# powermeter.net
KiCad netlist of a schematic drawn in EAGLE
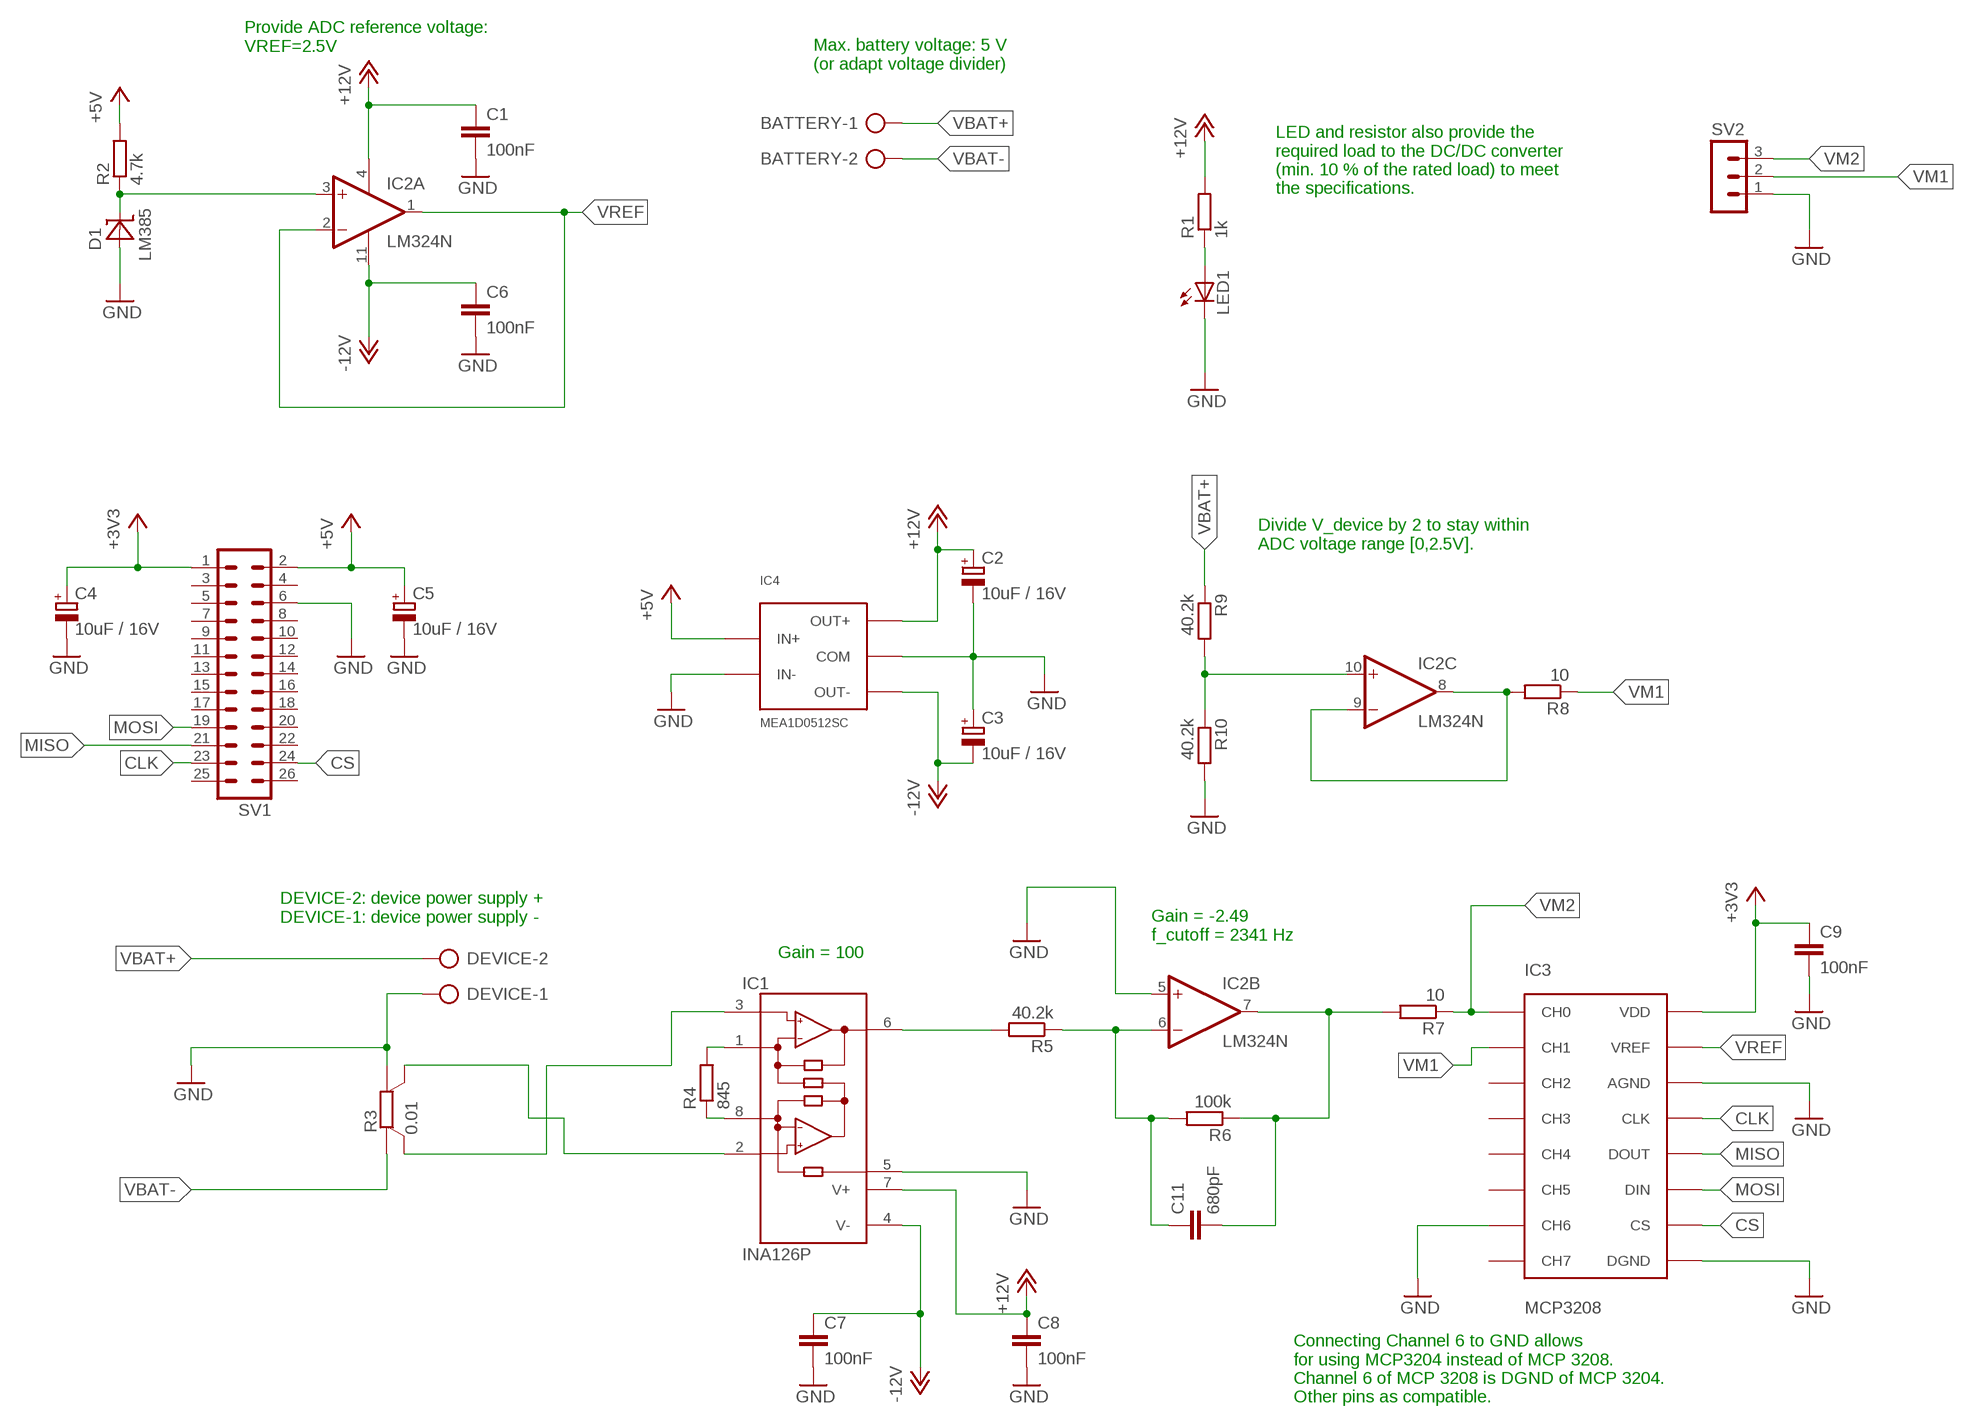
[diagram p0: schematic, sheet 1]

(export (version "E")
  (design (tool "Eeschema 10.0.6"))
  (components
    (comp (ref "BATTERY")
      (value "AK500/2")
      (footprint "eagle-import:AK500_2")
      (libsource (lib "eagle-import") (part "AK500/2"))
    )
    (comp (ref "C1")
      (value "100nF")
      (footprint "eagle-import:C050-024X044")
      (libsource (lib "eagle-import") (part "C-EU050-024X044"))
    )
    (comp (ref "C2")
      (value "10uF / 16V")
      (footprint "eagle-import:E2,5-6")
      (libsource (lib "eagle-import") (part "CPOL-EUE2.5-6"))
    )
    (comp (ref "C3")
      (value "10uF / 16V")
      (footprint "eagle-import:E2,5-6")
      (libsource (lib "eagle-import") (part "CPOL-EUE2.5-6"))
    )
    (comp (ref "C4")
      (value "10uF / 16V")
      (footprint "eagle-import:E2,5-6")
      (libsource (lib "eagle-import") (part "CPOL-EUE2.5-6"))
    )
    (comp (ref "C5")
      (value "10uF / 16V")
      (footprint "eagle-import:E2,5-6")
      (libsource (lib "eagle-import") (part "CPOL-EUE2.5-6"))
    )
    (comp (ref "C6")
      (value "100nF")
      (footprint "eagle-import:C050-024X044")
      (libsource (lib "eagle-import") (part "C-EU050-024X044"))
    )
    (comp (ref "C7")
      (value "100nF")
      (footprint "eagle-import:C050-024X044")
      (libsource (lib "eagle-import") (part "C-EU050-024X044"))
    )
    (comp (ref "C8")
      (value "100nF")
      (footprint "eagle-import:C050-024X044")
      (libsource (lib "eagle-import") (part "C-EU050-024X044"))
    )
    (comp (ref "C9")
      (value "100nF")
      (footprint "eagle-import:C050-024X044")
      (libsource (lib "eagle-import") (part "C-EU050-024X044"))
    )
    (comp (ref "C11")
      (value "680pF")
      (footprint "eagle-import:C050-050X075")
      (libsource (lib "eagle-import") (part "C-EU050-050X075"))
    )
    (comp (ref "D1")
      (value "LM385")
      (footprint "eagle-import:TO-92")
      (libsource (lib "eagle-import") (part "LM385"))
    )
    (comp (ref "DEVICE")
      (value "AK500/2")
      (footprint "eagle-import:AK500_2")
      (libsource (lib "eagle-import") (part "AK500/2"))
    )
    (comp (ref "IC1")
      (value "INA126P")
      (footprint "eagle-import:DIL08")
      (fields (field (name "MF") "TEXAS INSTRUMENT CONNECTORS"))
      (libsource (lib "eagle-import") (part "INA126P"))
    )
    (comp (ref "IC2")
      (value "LM324N")
      (footprint "eagle-import:DIL14")
      (libsource (lib "eagle-import") (part "LM324N"))
    )
    (comp (ref "IC3")
      (value "MCP3208")
      (footprint "eagle-import:DIL16")
      (libsource (lib "eagle-import") (part "MCP3208"))
    )
    (comp (ref "IC4")
      (value "MEA1D0512SC")
      (footprint "eagle-import:MEA1")
      (libsource (lib "eagle-import") (part "MEA1"))
    )
    (comp (ref "LED1")
      (value "LED3MM")
      (footprint "eagle-import:LED3MM")
      (libsource (lib "eagle-import") (part "LED3MM"))
    )
    (comp (ref "R1")
      (value "1k")
      (footprint "eagle-import:0207_7")
      (libsource (lib "eagle-import") (part "R-EU_0207/7"))
    )
    (comp (ref "R2")
      (value "4.7k")
      (footprint "eagle-import:0207_7")
      (libsource (lib "eagle-import") (part "R-EU_0207/7"))
    )
    (comp (ref "R3")
      (value "0.01")
      (footprint "eagle-import:PBV")
      (libsource (lib "eagle-import") (part "PBV"))
    )
    (comp (ref "R4")
      (value "845")
      (footprint "eagle-import:0207_7")
      (libsource (lib "eagle-import") (part "R-EU_0207/7"))
    )
    (comp (ref "R5")
      (value "40.2k")
      (footprint "eagle-import:0207_7")
      (libsource (lib "eagle-import") (part "R-EU_0207/7"))
    )
    (comp (ref "R6")
      (value "100k")
      (footprint "eagle-import:0207_7")
      (libsource (lib "eagle-import") (part "R-EU_0207/7"))
    )
    (comp (ref "R7")
      (value "10")
      (footprint "eagle-import:0207_7")
      (libsource (lib "eagle-import") (part "R-EU_0207/7"))
    )
    (comp (ref "R8")
      (value "10")
      (footprint "eagle-import:0207_7")
      (libsource (lib "eagle-import") (part "R-EU_0207/7"))
    )
    (comp (ref "R9")
      (value "40.2k")
      (footprint "eagle-import:0207_7")
      (libsource (lib "eagle-import") (part "R-EU_0207/7"))
    )
    (comp (ref "R10")
      (value "40.2k")
      (footprint "eagle-import:0207_7")
      (libsource (lib "eagle-import") (part "R-EU_0207/7"))
    )
    (comp (ref "SV1")
      (value "ML26")
      (footprint "eagle-import:ML26")
      (libsource (lib "eagle-import") (part "ML26"))
    )
    (comp (ref "SV2")
      (value "MA03-1")
      (footprint "eagle-import:MA03-1")
      (libsource (lib "eagle-import") (part "MA03-1"))
    )
  )
  (nets
    (net (code "1") (name "+3V3") (class "Default")
      (node (ref "C4") (pin "+") (pinfunction "+_+") (pintype "passive"))
      (node (ref "C9") (pin "1") (pinfunction "1_1") (pintype "passive"))
      (node (ref "IC3") (pin "VDD") (pinfunction "VDD_VDD") (pintype "power_in"))
      (node (ref "SV1") (pin "1") (pinfunction "1_1") (pintype "passive"))
    )
    (net (code "2") (name "+5V") (class "Default")
      (node (ref "C5") (pin "+") (pinfunction "+_+") (pintype "passive"))
      (node (ref "IC4") (pin "P$IN+") (pinfunction "IN+_P$IN+") (pintype "power_in"))
      (node (ref "R2") (pin "2") (pinfunction "2_2") (pintype "passive"))
      (node (ref "SV1") (pin "2") (pinfunction "2_2") (pintype "passive"))
    )
    (net (code "3") (name "+12V") (class "Default")
      (node (ref "C1") (pin "1") (pinfunction "1_1") (pintype "passive"))
      (node (ref "C2") (pin "+") (pinfunction "+_+") (pintype "passive"))
      (node (ref "C8") (pin "1") (pinfunction "1_1") (pintype "passive"))
      (node (ref "IC1") (pin "7") (pinfunction "V+_7") (pintype "power_in"))
      (node (ref "IC2") (pin "4") (pinfunction "V+_4") (pintype "power_in"))
      (node (ref "IC4") (pin "P$OUT+") (pinfunction "OUT+_P$OUT+") (pintype "power_in"))
      (node (ref "R1") (pin "2") (pinfunction "2_2") (pintype "passive"))
    )
    (net (code "4") (name "-12V") (class "Default")
      (node (ref "C3") (pin "-") (pinfunction "-_-") (pintype "passive"))
      (node (ref "C6") (pin "1") (pinfunction "1_1") (pintype "passive"))
      (node (ref "C7") (pin "1") (pinfunction "1_1") (pintype "passive"))
      (node (ref "IC1") (pin "4") (pinfunction "V-_4") (pintype "power_in"))
      (node (ref "IC2") (pin "11") (pinfunction "V-_11") (pintype "power_in"))
      (node (ref "IC4") (pin "P$OUT-") (pinfunction "OUT-_P$OUT-") (pintype "power_in"))
    )
    (net (code "5") (name "CLK") (class "Default")
      (node (ref "IC3") (pin "CLK") (pinfunction "CLK_CLK") (pintype "input"))
      (node (ref "SV1") (pin "23") (pinfunction "23_23") (pintype "passive"))
    )
    (net (code "6") (name "CS") (class "Default")
      (node (ref "IC3") (pin "CS") (pinfunction "CS_CS") (pintype "input"))
      (node (ref "SV1") (pin "24") (pinfunction "24_24") (pintype "passive"))
    )
    (net (code "7") (name "GND") (class "Default")
      (node (ref "C1") (pin "2") (pinfunction "2_2") (pintype "passive"))
      (node (ref "C2") (pin "-") (pinfunction "-_-") (pintype "passive"))
      (node (ref "C3") (pin "+") (pinfunction "+_+") (pintype "passive"))
      (node (ref "C4") (pin "-") (pinfunction "-_-") (pintype "passive"))
      (node (ref "C5") (pin "-") (pinfunction "-_-") (pintype "passive"))
      (node (ref "C6") (pin "2") (pinfunction "2_2") (pintype "passive"))
      (node (ref "C7") (pin "2") (pinfunction "2_2") (pintype "passive"))
      (node (ref "C8") (pin "2") (pinfunction "2_2") (pintype "passive"))
      (node (ref "C9") (pin "2") (pinfunction "2_2") (pintype "passive"))
      (node (ref "D1") (pin "+") (pinfunction "+_+") (pintype "passive"))
      (node (ref "DEVICE") (pin "1") (pinfunction "KL_1") (pintype "passive"))
      (node (ref "IC1") (pin "5") (pinfunction "REF_5") (pintype "passive"))
      (node (ref "IC2") (pin "5") (pinfunction "+IN_5") (pintype "input"))
      (node (ref "IC3") (pin "AGND") (pinfunction "AGND_AGND") (pintype "power_in"))
      (node (ref "IC3") (pin "CH6") (pinfunction "CH6_CH6") (pintype "input"))
      (node (ref "IC3") (pin "DGND") (pinfunction "DGND_DGND") (pintype "power_in"))
      (node (ref "IC4") (pin "P$COM") (pinfunction "COM_P$COM") (pintype "power_in"))
      (node (ref "IC4") (pin "P$IN-") (pinfunction "IN-_P$IN-") (pintype "power_in"))
      (node (ref "LED1") (pin "K") (pinfunction "C_K") (pintype "passive"))
      (node (ref "R10") (pin "2") (pinfunction "2_2") (pintype "passive"))
      (node (ref "R3") (pin "P$A") (pinfunction "A_P$A") (pintype "passive"))
      (node (ref "SV1") (pin "6") (pinfunction "6_6") (pintype "passive"))
      (node (ref "SV2") (pin "1") (pinfunction "1_1") (pintype "passive"))
    )
    (net (code "8") (name "MISO") (class "Default")
      (node (ref "IC3") (pin "DOUT") (pinfunction "DOUT_DOUT") (pintype "output"))
      (node (ref "SV1") (pin "21") (pinfunction "21_21") (pintype "passive"))
    )
    (net (code "9") (name "MOSI") (class "Default")
      (node (ref "IC3") (pin "DIN") (pinfunction "DIN_DIN") (pintype "input"))
      (node (ref "SV1") (pin "19") (pinfunction "19_19") (pintype "passive"))
    )
    (net (code "10") (name "Net-(IC1-+IN)") (class "Default")
      (node (ref "IC1") (pin "3") (pinfunction "+IN_3") (pintype "input"))
      (node (ref "R3") (pin "P$SB") (pinfunction "SB_P$SB") (pintype "passive"))
    )
    (net (code "11") (name "Net-(IC1--IN)") (class "Default")
      (node (ref "IC1") (pin "2") (pinfunction "-IN_2") (pintype "input"))
      (node (ref "R3") (pin "P$SA") (pinfunction "SA_P$SA") (pintype "passive"))
    )
    (net (code "12") (name "Net-(IC1-OUT)") (class "Default")
      (node (ref "IC1") (pin "6") (pinfunction "OUT_6") (pintype "output"))
      (node (ref "R5") (pin "2") (pinfunction "2_2") (pintype "passive"))
    )
    (net (code "13") (name "Net-(IC1-RG-Pad1)") (class "Default")
      (node (ref "IC1") (pin "1") (pinfunction "RG_1") (pintype "passive"))
      (node (ref "R4") (pin "2") (pinfunction "2_2") (pintype "passive"))
    )
    (net (code "14") (name "Net-(IC1-RG-Pad8)") (class "Default")
      (node (ref "IC1") (pin "8") (pinfunction "RG_8") (pintype "passive"))
      (node (ref "R4") (pin "1") (pinfunction "1_1") (pintype "passive"))
    )
    (net (code "15") (name "Net-(IC2A-+IN)") (class "Default")
      (node (ref "D1") (pin "-") (pinfunction "-_-") (pintype "passive"))
      (node (ref "IC2") (pin "3") (pinfunction "+IN_3") (pintype "input"))
      (node (ref "R2") (pin "1") (pinfunction "1_1") (pintype "passive"))
    )
    (net (code "16") (name "Net-(IC2B--IN)") (class "Default")
      (node (ref "C11") (pin "1") (pinfunction "1_1") (pintype "passive"))
      (node (ref "IC2") (pin "6") (pinfunction "-IN_6") (pintype "input"))
      (node (ref "R5") (pin "1") (pinfunction "1_1") (pintype "passive"))
      (node (ref "R6") (pin "2") (pinfunction "2_2") (pintype "passive"))
    )
    (net (code "17") (name "Net-(IC2B-OUT)") (class "Default")
      (node (ref "C11") (pin "2") (pinfunction "2_2") (pintype "passive"))
      (node (ref "IC2") (pin "7") (pinfunction "OUT_7") (pintype "output"))
      (node (ref "R6") (pin "1") (pinfunction "1_1") (pintype "passive"))
      (node (ref "R7") (pin "2") (pinfunction "2_2") (pintype "passive"))
    )
    (net (code "18") (name "Net-(IC2C-+IN)") (class "Default")
      (node (ref "IC2") (pin "10") (pinfunction "+IN_10") (pintype "input"))
      (node (ref "R10") (pin "1") (pinfunction "1_1") (pintype "passive"))
      (node (ref "R9") (pin "2") (pinfunction "2_2") (pintype "passive"))
    )
    (net (code "19") (name "Net-(IC2C--IN)") (class "Default")
      (node (ref "IC2") (pin "8") (pinfunction "OUT_8") (pintype "output"))
      (node (ref "IC2") (pin "9") (pinfunction "-IN_9") (pintype "input"))
      (node (ref "R8") (pin "2") (pinfunction "2_2") (pintype "passive"))
    )
    (net (code "20") (name "Net-(LED1-PadA)") (class "Default")
      (node (ref "LED1") (pin "A") (pinfunction "A_A") (pintype "passive"))
      (node (ref "R1") (pin "1") (pinfunction "1_1") (pintype "passive"))
    )
    (net (code "21") (name "VBAT+") (class "Default")
      (node (ref "BATTERY") (pin "1") (pinfunction "KL_1") (pintype "passive"))
      (node (ref "DEVICE") (pin "2") (pinfunction "KL_2") (pintype "passive"))
      (node (ref "R9") (pin "1") (pinfunction "1_1") (pintype "passive"))
    )
    (net (code "22") (name "VBAT-") (class "Default")
      (node (ref "BATTERY") (pin "2") (pinfunction "KL_2") (pintype "passive"))
      (node (ref "R3") (pin "P$B") (pinfunction "B_P$B") (pintype "passive"))
    )
    (net (code "23") (name "VM1") (class "Default")
      (node (ref "IC3") (pin "CH1") (pinfunction "CH1_CH1") (pintype "input"))
      (node (ref "R8") (pin "1") (pinfunction "1_1") (pintype "passive"))
      (node (ref "SV2") (pin "2") (pinfunction "2_2") (pintype "passive"))
    )
    (net (code "24") (name "VM2") (class "Default")
      (node (ref "IC3") (pin "CH0") (pinfunction "CH0_CH0") (pintype "input"))
      (node (ref "R7") (pin "1") (pinfunction "1_1") (pintype "passive"))
      (node (ref "SV2") (pin "3") (pinfunction "3_3") (pintype "passive"))
    )
    (net (code "25") (name "VREF") (class "Default")
      (node (ref "IC2") (pin "1") (pinfunction "OUT_1") (pintype "output"))
      (node (ref "IC2") (pin "2") (pinfunction "-IN_2") (pintype "input"))
      (node (ref "IC3") (pin "VREF") (pinfunction "VREF_VREF") (pintype "input"))
    )
    (net (code "26") (name "unconnected-(IC3-PadCH2)") (class "Default")
      (node (ref "IC3") (pin "CH2") (pinfunction "CH2_CH2") (pintype "input"))
    )
    (net (code "27") (name "unconnected-(IC3-PadCH3)") (class "Default")
      (node (ref "IC3") (pin "CH3") (pinfunction "CH3_CH3") (pintype "input"))
    )
    (net (code "28") (name "unconnected-(IC3-PadCH4)") (class "Default")
      (node (ref "IC3") (pin "CH4") (pinfunction "CH4_CH4") (pintype "input"))
    )
    (net (code "29") (name "unconnected-(IC3-PadCH5)") (class "Default")
      (node (ref "IC3") (pin "CH5") (pinfunction "CH5_CH5") (pintype "input"))
    )
    (net (code "30") (name "unconnected-(IC3-PadCH7)") (class "Default")
      (node (ref "IC3") (pin "CH7") (pinfunction "CH7_CH7") (pintype "input"))
    )
    (net (code "31") (name "unconnected-(SV1-Pad3)") (class "Default")
      (node (ref "SV1") (pin "3") (pinfunction "3_3") (pintype "passive"))
    )
    (net (code "32") (name "unconnected-(SV1-Pad4)") (class "Default")
      (node (ref "SV1") (pin "4") (pinfunction "4_4") (pintype "passive"))
    )
    (net (code "33") (name "unconnected-(SV1-Pad5)") (class "Default")
      (node (ref "SV1") (pin "5") (pinfunction "5_5") (pintype "passive"))
    )
    (net (code "34") (name "unconnected-(SV1-Pad7)") (class "Default")
      (node (ref "SV1") (pin "7") (pinfunction "7_7") (pintype "passive"))
    )
    (net (code "35") (name "unconnected-(SV1-Pad8)") (class "Default")
      (node (ref "SV1") (pin "8") (pinfunction "8_8") (pintype "passive"))
    )
    (net (code "36") (name "unconnected-(SV1-Pad9)") (class "Default")
      (node (ref "SV1") (pin "9") (pinfunction "9_9") (pintype "passive"))
    )
    (net (code "37") (name "unconnected-(SV1-Pad10)") (class "Default")
      (node (ref "SV1") (pin "10") (pinfunction "10_10") (pintype "passive"))
    )
    (net (code "38") (name "unconnected-(SV1-Pad11)") (class "Default")
      (node (ref "SV1") (pin "11") (pinfunction "11_11") (pintype "passive"))
    )
    (net (code "39") (name "unconnected-(SV1-Pad12)") (class "Default")
      (node (ref "SV1") (pin "12") (pinfunction "12_12") (pintype "passive"))
    )
    (net (code "40") (name "unconnected-(SV1-Pad13)") (class "Default")
      (node (ref "SV1") (pin "13") (pinfunction "13_13") (pintype "passive"))
    )
    (net (code "41") (name "unconnected-(SV1-Pad14)") (class "Default")
      (node (ref "SV1") (pin "14") (pinfunction "14_14") (pintype "passive"))
    )
    (net (code "42") (name "unconnected-(SV1-Pad15)") (class "Default")
      (node (ref "SV1") (pin "15") (pinfunction "15_15") (pintype "passive"))
    )
    (net (code "43") (name "unconnected-(SV1-Pad16)") (class "Default")
      (node (ref "SV1") (pin "16") (pinfunction "16_16") (pintype "passive"))
    )
    (net (code "44") (name "unconnected-(SV1-Pad17)") (class "Default")
      (node (ref "SV1") (pin "17") (pinfunction "17_17") (pintype "passive"))
    )
    (net (code "45") (name "unconnected-(SV1-Pad18)") (class "Default")
      (node (ref "SV1") (pin "18") (pinfunction "18_18") (pintype "passive"))
    )
    (net (code "46") (name "unconnected-(SV1-Pad20)") (class "Default")
      (node (ref "SV1") (pin "20") (pinfunction "20_20") (pintype "passive"))
    )
    (net (code "47") (name "unconnected-(SV1-Pad22)") (class "Default")
      (node (ref "SV1") (pin "22") (pinfunction "22_22") (pintype "passive"))
    )
    (net (code "48") (name "unconnected-(SV1-Pad25)") (class "Default")
      (node (ref "SV1") (pin "25") (pinfunction "25_25") (pintype "passive"))
    )
    (net (code "49") (name "unconnected-(SV1-Pad26)") (class "Default")
      (node (ref "SV1") (pin "26") (pinfunction "26_26") (pintype "passive"))
    )
  )
)
